# scard.net
KiCad netlist of a schematic drawn in EAGLE
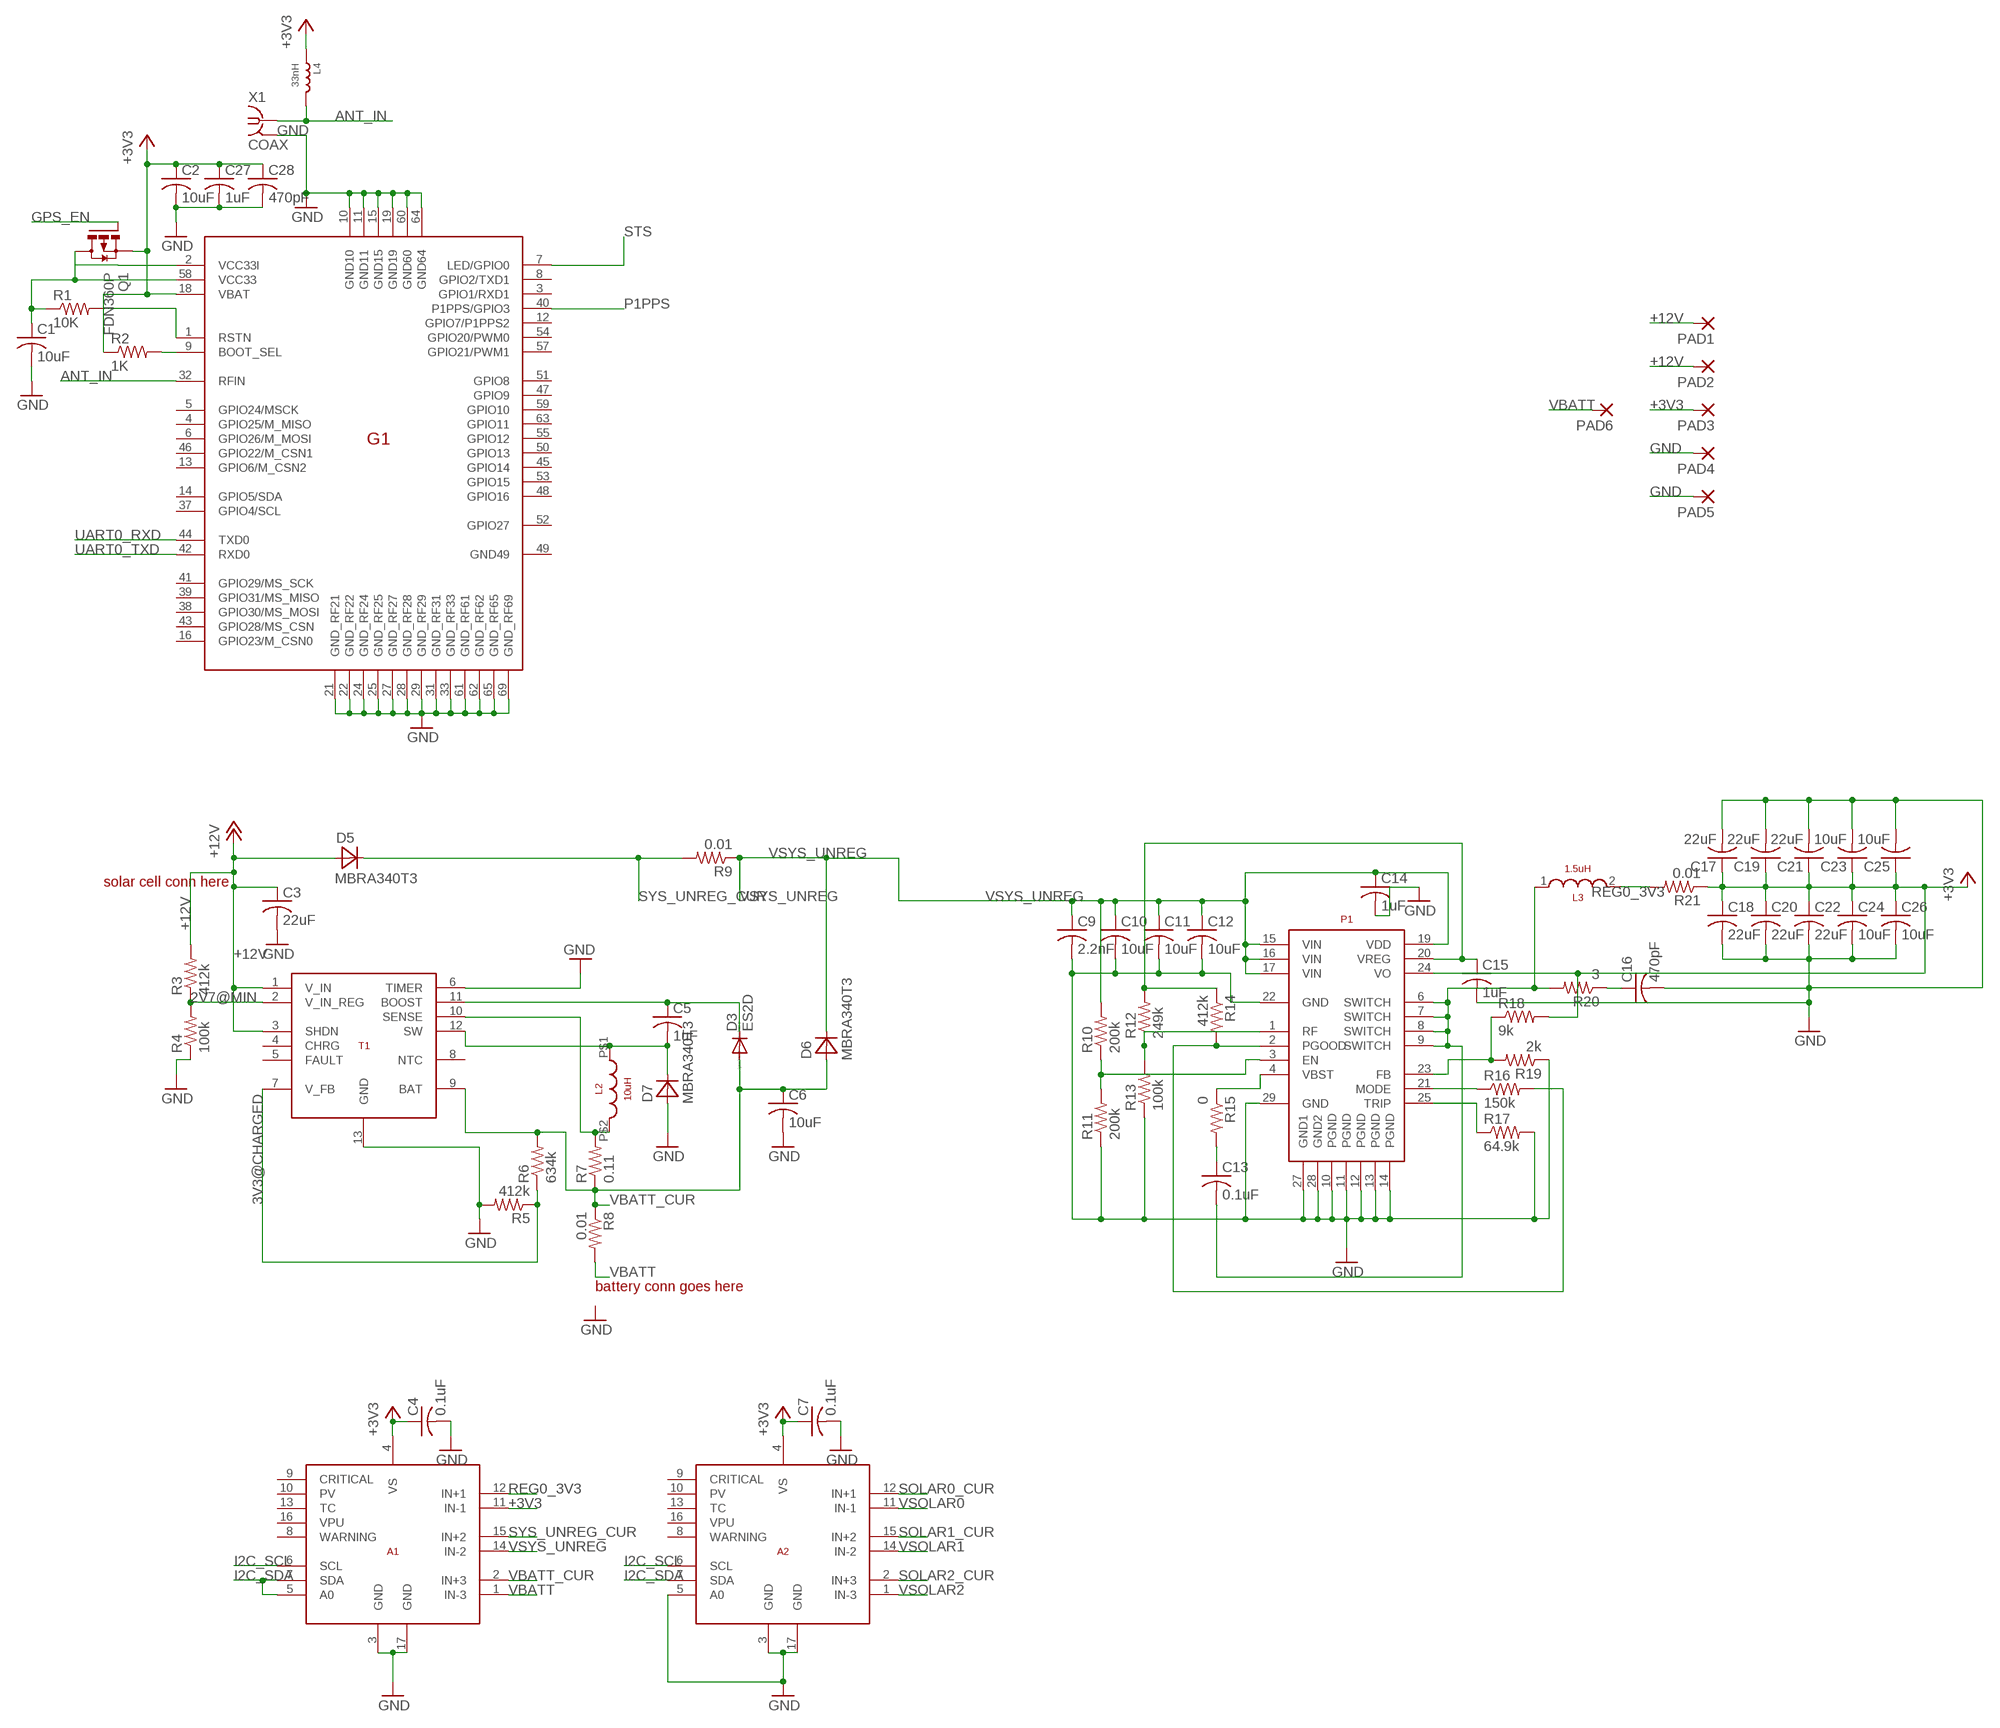
[diagram p0: schematic, sheet 1]

(export (version "E")
  (design (tool "Eeschema 10.0.6"))
  (components
    (comp (ref "A1")
      (value "INA3221-Q1")
      (footprint "eagle-import:VQFN16")
      (libsource (lib "eagle-import") (part "INA3221-Q1"))
    )
    (comp (ref "A2")
      (value "INA3221-Q1")
      (footprint "eagle-import:VQFN16")
      (libsource (lib "eagle-import") (part "INA3221-Q1"))
    )
    (comp (ref "C1")
      (value "10uF")
      (footprint "eagle-import:C0603")
      (libsource (lib "eagle-import") (part "C-USC0603"))
    )
    (comp (ref "C2")
      (value "10uF")
      (footprint "eagle-import:C0603")
      (libsource (lib "eagle-import") (part "resistor_348_C-USC0603"))
    )
    (comp (ref "C3")
      (value "22uF")
      (footprint "eagle-import:C0805")
      (libsource (lib "eagle-import") (part "resistor_348_C-USC0805"))
    )
    (comp (ref "C4")
      (value "0.1uF")
      (footprint "eagle-import:C0603")
      (libsource (lib "eagle-import") (part "resistor_348_C-USC0603"))
    )
    (comp (ref "C5")
      (value "1uF")
      (footprint "eagle-import:C0402")
      (libsource (lib "eagle-import") (part "C-USC0402"))
    )
    (comp (ref "C6")
      (value "10uF")
      (footprint "eagle-import:C0805")
      (libsource (lib "eagle-import") (part "resistor_348_C-USC0805"))
    )
    (comp (ref "C7")
      (value "0.1uF")
      (footprint "eagle-import:C0603")
      (libsource (lib "eagle-import") (part "resistor_348_C-USC0603"))
    )
    (comp (ref "C9")
      (value "2.2nF")
      (footprint "eagle-import:C0402")
      (libsource (lib "eagle-import") (part "resistor_348_C-USC0402"))
    )
    (comp (ref "C10")
      (value "10uF")
      (footprint "eagle-import:C0603")
      (libsource (lib "eagle-import") (part "resistor_348_C-USC0603"))
    )
    (comp (ref "C11")
      (value "10uF")
      (footprint "eagle-import:C0603")
      (libsource (lib "eagle-import") (part "resistor_348_C-USC0603"))
    )
    (comp (ref "C12")
      (value "10uF")
      (footprint "eagle-import:C0603")
      (libsource (lib "eagle-import") (part "resistor_348_C-USC0603"))
    )
    (comp (ref "C13")
      (value "0.1uF")
      (footprint "eagle-import:C0402")
      (libsource (lib "eagle-import") (part "resistor_348_C-USC0402"))
    )
    (comp (ref "C14")
      (value "1uF")
      (footprint "eagle-import:C0402")
      (libsource (lib "eagle-import") (part "resistor_348_C-USC0402"))
    )
    (comp (ref "C15")
      (value "1uF")
      (footprint "eagle-import:C0402")
      (libsource (lib "eagle-import") (part "resistor_348_C-USC0402"))
    )
    (comp (ref "C16")
      (value "470pF")
      (footprint "eagle-import:C0402")
      (libsource (lib "eagle-import") (part "resistor_348_C-USC0402"))
    )
    (comp (ref "C17")
      (value "22uF")
      (footprint "eagle-import:C0805")
      (libsource (lib "eagle-import") (part "C-USC0805"))
    )
    (comp (ref "C18")
      (value "22uF")
      (footprint "eagle-import:C0805")
      (libsource (lib "eagle-import") (part "C-USC0805"))
    )
    (comp (ref "C19")
      (value "22uF")
      (footprint "eagle-import:C0805")
      (libsource (lib "eagle-import") (part "C-USC0805"))
    )
    (comp (ref "C20")
      (value "22uF")
      (footprint "eagle-import:C0805")
      (libsource (lib "eagle-import") (part "C-USC0805"))
    )
    (comp (ref "C21")
      (value "22uF")
      (footprint "eagle-import:C0805")
      (libsource (lib "eagle-import") (part "C-USC0805"))
    )
    (comp (ref "C22")
      (value "22uF")
      (footprint "eagle-import:C0805")
      (libsource (lib "eagle-import") (part "C-USC0805"))
    )
    (comp (ref "C23")
      (value "10uF")
      (footprint "eagle-import:C0603")
      (libsource (lib "eagle-import") (part "resistor_348_C-USC0603"))
    )
    (comp (ref "C24")
      (value "10uF")
      (footprint "eagle-import:C0603")
      (libsource (lib "eagle-import") (part "resistor_348_C-USC0603"))
    )
    (comp (ref "C25")
      (value "10uF")
      (footprint "eagle-import:C0603")
      (libsource (lib "eagle-import") (part "resistor_348_C-USC0603"))
    )
    (comp (ref "C26")
      (value "10uF")
      (footprint "eagle-import:C0603")
      (libsource (lib "eagle-import") (part "resistor_348_C-USC0603"))
    )
    (comp (ref "C27")
      (value "1uF")
      (footprint "eagle-import:C0402")
      (libsource (lib "eagle-import") (part "resistor_348_C-USC0402"))
    )
    (comp (ref "C28")
      (value "470pF")
      (footprint "eagle-import:C0402")
      (libsource (lib "eagle-import") (part "resistor_348_C-USC0402"))
    )
    (comp (ref "D3")
      (value "ES2D")
      (footprint "eagle-import:SMB")
      (libsource (lib "eagle-import") (part "ES2D"))
    )
    (comp (ref "D5")
      (value "MBRA340T3")
      (footprint "eagle-import:SMA")
      (libsource (lib "eagle-import") (part "MBRA340T3"))
    )
    (comp (ref "D6")
      (value "MBRA340T3")
      (footprint "eagle-import:SMA")
      (libsource (lib "eagle-import") (part "MBRA340T3"))
    )
    (comp (ref "D7")
      (value "MBRA340T3")
      (footprint "eagle-import:SMA")
      (libsource (lib "eagle-import") (part "MBRA340T3"))
    )
    (comp (ref "G1")
      (value "VENUS838FLPX-L")
      (footprint "eagle-import:LGA69")
      (libsource (lib "eagle-import") (part "VENUS838FLPX-L"))
    )
    (comp (ref "L2")
      (value "10uH")
      (footprint "eagle-import:SRP7030")
      (libsource (lib "eagle-import") (part "SRP7030-100M"))
    )
    (comp (ref "L3")
      (value "1.5uH")
      (footprint "eagle-import:SRP7028A")
      (libsource (lib "eagle-import") (part "SRP7028A"))
    )
    (comp (ref "L4")
      (value "33nH")
      (footprint "eagle-import:L0805")
      (fields (field (name "MPN") "BLM21PG331SN1D"))
      (libsource (lib "eagle-import") (part "SMD-FERRITE-BEAD-330R-1500MA(0805)'0805'"))
    )
    (comp (ref "P1")
      (value "TPS548A20")
      (footprint "eagle-import:R-PWQFN-N28")
      (libsource (lib "eagle-import") (part "TPS548A20"))
    )
    (comp (ref "PAD1")
      (value "SMD5")
      (footprint "eagle-import:SMD2,54-5,08")
      (libsource (lib "eagle-import") (part "SMD5"))
    )
    (comp (ref "PAD2")
      (value "SMD5")
      (footprint "eagle-import:SMD2,54-5,08")
      (libsource (lib "eagle-import") (part "SMD5"))
    )
    (comp (ref "PAD3")
      (value "SMD5")
      (footprint "eagle-import:SMD2,54-5,08")
      (libsource (lib "eagle-import") (part "SMD5"))
    )
    (comp (ref "PAD4")
      (value "SMD5")
      (footprint "eagle-import:SMD2,54-5,08")
      (libsource (lib "eagle-import") (part "SMD5"))
    )
    (comp (ref "PAD5")
      (value "SMD5")
      (footprint "eagle-import:SMD2,54-5,08")
      (libsource (lib "eagle-import") (part "SMD5"))
    )
    (comp (ref "PAD6")
      (value "SMD5")
      (footprint "eagle-import:SMD2,54-5,08")
      (libsource (lib "eagle-import") (part "SMD5"))
    )
    (comp (ref "Q1")
      (value "FDN360P")
      (footprint "eagle-import:SUPER-SOT3")
      (libsource (lib "eagle-import") (part "FDN360P"))
    )
    (comp (ref "R1")
      (value "10K")
      (footprint "eagle-import:R0603")
      (libsource (lib "eagle-import") (part "R-US_R0603"))
    )
    (comp (ref "R2")
      (value "1K")
      (footprint "eagle-import:R0603")
      (libsource (lib "eagle-import") (part "resistor_348_R-US_R0603"))
    )
    (comp (ref "R3")
      (value "412k")
      (footprint "eagle-import:R0603")
      (libsource (lib "eagle-import") (part "R-US_R0603"))
    )
    (comp (ref "R4")
      (value "100k")
      (footprint "eagle-import:R0603")
      (libsource (lib "eagle-import") (part "R-US_R0603"))
    )
    (comp (ref "R5")
      (value "412k")
      (footprint "eagle-import:R0603")
      (libsource (lib "eagle-import") (part "R-US_R0603"))
    )
    (comp (ref "R6")
      (value "634k")
      (footprint "eagle-import:R0603")
      (libsource (lib "eagle-import") (part "R-US_R0603"))
    )
    (comp (ref "R7")
      (value "0.11")
      (footprint "eagle-import:R0603")
      (libsource (lib "eagle-import") (part "R-US_R0603"))
    )
    (comp (ref "R8")
      (value "0.01")
      (footprint "eagle-import:R0603")
      (libsource (lib "eagle-import") (part "R-US_R0603"))
    )
    (comp (ref "R9")
      (value "0.01")
      (footprint "eagle-import:R0603")
      (libsource (lib "eagle-import") (part "R-US_R0603"))
    )
    (comp (ref "R10")
      (value "200k")
      (footprint "eagle-import:R0603")
      (libsource (lib "eagle-import") (part "R-US_R0603"))
    )
    (comp (ref "R11")
      (value "200k")
      (footprint "eagle-import:R0603")
      (libsource (lib "eagle-import") (part "R-US_R0603"))
    )
    (comp (ref "R12")
      (value "249k")
      (footprint "eagle-import:R0603")
      (libsource (lib "eagle-import") (part "R-US_R0603"))
    )
    (comp (ref "R13")
      (value "100k")
      (footprint "eagle-import:R0603")
      (libsource (lib "eagle-import") (part "R-US_R0603"))
    )
    (comp (ref "R14")
      (value "412k")
      (footprint "eagle-import:R0603")
      (libsource (lib "eagle-import") (part "R-US_R0603"))
    )
    (comp (ref "R15")
      (value "0")
      (footprint "eagle-import:R0603")
      (libsource (lib "eagle-import") (part "R-US_R0603"))
    )
    (comp (ref "R16")
      (value "150k")
      (footprint "eagle-import:R0603")
      (libsource (lib "eagle-import") (part "R-US_R0603"))
    )
    (comp (ref "R17")
      (value "64.9k")
      (footprint "eagle-import:R0603")
      (libsource (lib "eagle-import") (part "R-US_R0603"))
    )
    (comp (ref "R18")
      (value "9k")
      (footprint "eagle-import:R0603")
      (libsource (lib "eagle-import") (part "R-US_R0603"))
    )
    (comp (ref "R19")
      (value "2k")
      (footprint "eagle-import:R0603")
      (libsource (lib "eagle-import") (part "R-US_R0603"))
    )
    (comp (ref "R20")
      (value "3")
      (footprint "eagle-import:R0603")
      (libsource (lib "eagle-import") (part "R-US_R0603"))
    )
    (comp (ref "R21")
      (value "0.01")
      (footprint "eagle-import:R0603")
      (libsource (lib "eagle-import") (part "R-US_R0603"))
    )
    (comp (ref "T1")
      (value "LT3652")
      (footprint "eagle-import:MSOP12")
      (libsource (lib "eagle-import") (part "LT3652"))
    )
    (comp (ref "X1")
      (value "COAX")
      (footprint "eagle-import:MMCX-J-P-X-ST-EM1-MKT")
      (libsource (lib "eagle-import") (part "COAX"))
    )
  )
  (nets
    (net (code "1") (name "+3V3") (class "Default")
      (node (ref "A1") (pin "11") (pinfunction "IN-1_11") (pintype "input"))
      (node (ref "A1") (pin "4") (pinfunction "VS_4") (pintype "power_in"))
      (node (ref "A2") (pin "4") (pinfunction "VS_4") (pintype "power_in"))
      (node (ref "C17") (pin "1") (pinfunction "1_1") (pintype "passive"))
      (node (ref "C18") (pin "1") (pinfunction "1_1") (pintype "passive"))
      (node (ref "C19") (pin "1") (pinfunction "1_1") (pintype "passive"))
      (node (ref "C2") (pin "1") (pinfunction "1_1") (pintype "passive"))
      (node (ref "C20") (pin "1") (pinfunction "1_1") (pintype "passive"))
      (node (ref "C21") (pin "1") (pinfunction "1_1") (pintype "passive"))
      (node (ref "C22") (pin "1") (pinfunction "1_1") (pintype "passive"))
      (node (ref "C23") (pin "1") (pinfunction "1_1") (pintype "passive"))
      (node (ref "C24") (pin "1") (pinfunction "1_1") (pintype "passive"))
      (node (ref "C25") (pin "1") (pinfunction "1_1") (pintype "passive"))
      (node (ref "C26") (pin "1") (pinfunction "1_1") (pintype "passive"))
      (node (ref "C27") (pin "1") (pinfunction "1_1") (pintype "passive"))
      (node (ref "C28") (pin "1") (pinfunction "1_1") (pintype "passive"))
      (node (ref "C4") (pin "1") (pinfunction "1_1") (pintype "passive"))
      (node (ref "C7") (pin "1") (pinfunction "1_1") (pintype "passive"))
      (node (ref "G1") (pin "18") (pinfunction "VBAT_18") (pintype "bidirectional"))
      (node (ref "L4") (pin "1") (pinfunction "1_1") (pintype "passive"))
      (node (ref "P1") (pin "24") (pinfunction "VO_24") (pintype "input"))
      (node (ref "PAD3") (pin "1") (pinfunction "P_1") (pintype "passive"))
      (node (ref "Q1") (pin "2") (pinfunction "S_2") (pintype "passive"))
      (node (ref "R18") (pin "2") (pinfunction "2_2") (pintype "passive"))
      (node (ref "R2") (pin "1") (pinfunction "1_1") (pintype "passive"))
      (node (ref "R21") (pin "1") (pinfunction "1_1") (pintype "passive"))
    )
    (net (code "2") (name "+12V") (class "Default")
      (node (ref "C3") (pin "1") (pinfunction "1_1") (pintype "passive"))
      (node (ref "D5") (pin "A") (pinfunction "A_A") (pintype "passive"))
      (node (ref "PAD1") (pin "1") (pinfunction "P_1") (pintype "passive"))
      (node (ref "PAD2") (pin "1") (pinfunction "P_1") (pintype "passive"))
      (node (ref "R3") (pin "2") (pinfunction "2_2") (pintype "passive"))
      (node (ref "T1") (pin "1") (pinfunction "V_IN_1") (pintype "bidirectional"))
      (node (ref "T1") (pin "3") (pinfunction "SHDN_3") (pintype "bidirectional"))
    )
    (net (code "3") (name "/2V7@MIN") (class "Default")
      (node (ref "R3") (pin "1") (pinfunction "1_1") (pintype "passive"))
      (node (ref "R4") (pin "2") (pinfunction "2_2") (pintype "passive"))
      (node (ref "T1") (pin "2") (pinfunction "V_IN_REG_2") (pintype "bidirectional"))
    )
    (net (code "4") (name "/3V3@CHARGED") (class "Default")
      (node (ref "R5") (pin "1") (pinfunction "1_1") (pintype "passive"))
      (node (ref "R6") (pin "1") (pinfunction "1_1") (pintype "passive"))
      (node (ref "T1") (pin "7") (pinfunction "V_FB_7") (pintype "bidirectional"))
    )
    (net (code "5") (name "/ANT_IN") (class "Default")
      (node (ref "G1") (pin "32") (pinfunction "RFIN_32") (pintype "bidirectional"))
      (node (ref "L4") (pin "2") (pinfunction "2_2") (pintype "passive"))
      (node (ref "X1") (pin "1") (pinfunction "1_1") (pintype "passive"))
    )
    (net (code "6") (name "/GPS_EN") (class "Default")
      (node (ref "Q1") (pin "1") (pinfunction "G_1") (pintype "passive"))
    )
    (net (code "7") (name "/I2C_SCL") (class "Default")
      (node (ref "A1") (pin "6") (pinfunction "SCL_6") (pintype "bidirectional"))
      (node (ref "A2") (pin "6") (pinfunction "SCL_6") (pintype "bidirectional"))
    )
    (net (code "8") (name "/I2C_SDA") (class "Default")
      (node (ref "A1") (pin "5") (pinfunction "A0_5") (pintype "bidirectional"))
      (node (ref "A1") (pin "7") (pinfunction "SDA_7") (pintype "bidirectional"))
      (node (ref "A2") (pin "7") (pinfunction "SDA_7") (pintype "bidirectional"))
    )
    (net (code "9") (name "/P1PPS") (class "Default")
      (node (ref "G1") (pin "40") (pinfunction "P1PPS/GPIO3_40") (pintype "bidirectional"))
    )
    (net (code "10") (name "/REG0_3V3") (class "Default")
      (node (ref "A1") (pin "12") (pinfunction "IN+1_12") (pintype "input"))
      (node (ref "L3") (pin "2") (pintype "passive"))
      (node (ref "R21") (pin "2") (pinfunction "2_2") (pintype "passive"))
    )
    (net (code "11") (name "/SOLAR0_CUR") (class "Default")
      (node (ref "A2") (pin "12") (pinfunction "IN+1_12") (pintype "input"))
    )
    (net (code "12") (name "/SOLAR1_CUR") (class "Default")
      (node (ref "A2") (pin "15") (pinfunction "IN+2_15") (pintype "input"))
    )
    (net (code "13") (name "/SOLAR2_CUR") (class "Default")
      (node (ref "A2") (pin "2") (pinfunction "IN+3_2") (pintype "input"))
    )
    (net (code "14") (name "/STS") (class "Default")
      (node (ref "G1") (pin "7") (pinfunction "LED/GPIO0_7") (pintype "bidirectional"))
    )
    (net (code "15") (name "/SYS_UNREG_CUR") (class "Default")
      (node (ref "A1") (pin "15") (pinfunction "IN+2_15") (pintype "input"))
      (node (ref "D5") (pin "C") (pinfunction "C_C") (pintype "passive"))
      (node (ref "R9") (pin "2") (pinfunction "2_2") (pintype "passive"))
    )
    (net (code "16") (name "/UART0_RXD") (class "Default")
      (node (ref "G1") (pin "44") (pinfunction "TXD0_44") (pintype "bidirectional"))
    )
    (net (code "17") (name "/UART0_TXD") (class "Default")
      (node (ref "G1") (pin "42") (pinfunction "RXD0_42") (pintype "bidirectional"))
    )
    (net (code "18") (name "/VBATT") (class "Default")
      (node (ref "A1") (pin "1") (pinfunction "IN-3_1") (pintype "input"))
      (node (ref "PAD6") (pin "1") (pinfunction "P_1") (pintype "passive"))
      (node (ref "R8") (pin "2") (pinfunction "2_2") (pintype "passive"))
    )
    (net (code "19") (name "/VBATT_CUR") (class "Default")
      (node (ref "A1") (pin "2") (pinfunction "IN+3_2") (pintype "input"))
      (node (ref "C6") (pin "1") (pinfunction "1_1") (pintype "passive"))
      (node (ref "D3") (pin "A") (pinfunction "A_A") (pintype "passive"))
      (node (ref "D6") (pin "A") (pinfunction "A_A") (pintype "passive"))
      (node (ref "R6") (pin "2") (pinfunction "2_2") (pintype "passive"))
      (node (ref "R7") (pin "1") (pinfunction "1_1") (pintype "passive"))
      (node (ref "R8") (pin "1") (pinfunction "1_1") (pintype "passive"))
      (node (ref "T1") (pin "9") (pinfunction "BAT_9") (pintype "bidirectional"))
    )
    (net (code "20") (name "/VSOLAR0") (class "Default")
      (node (ref "A2") (pin "11") (pinfunction "IN-1_11") (pintype "input"))
    )
    (net (code "21") (name "/VSOLAR1") (class "Default")
      (node (ref "A2") (pin "14") (pinfunction "IN-2_14") (pintype "input"))
    )
    (net (code "22") (name "/VSOLAR2") (class "Default")
      (node (ref "A2") (pin "1") (pinfunction "IN-3_1") (pintype "input"))
    )
    (net (code "23") (name "/VSYS_UNREG") (class "Default")
      (node (ref "A1") (pin "14") (pinfunction "IN-2_14") (pintype "input"))
      (node (ref "C10") (pin "1") (pinfunction "1_1") (pintype "passive"))
      (node (ref "C11") (pin "1") (pinfunction "1_1") (pintype "passive"))
      (node (ref "C12") (pin "1") (pinfunction "1_1") (pintype "passive"))
      (node (ref "C14") (pin "1") (pinfunction "1_1") (pintype "passive"))
      (node (ref "C9") (pin "1") (pinfunction "1_1") (pintype "passive"))
      (node (ref "D6") (pin "C") (pinfunction "C_C") (pintype "passive"))
      (node (ref "P1") (pin "15") (pinfunction "VIN_15") (pintype "power_in"))
      (node (ref "P1") (pin "16") (pinfunction "VIN_16") (pintype "power_in"))
      (node (ref "P1") (pin "17") (pinfunction "VIN_17") (pintype "power_in"))
      (node (ref "P1") (pin "19") (pinfunction "VDD_19") (pintype "power_in"))
      (node (ref "R10") (pin "2") (pinfunction "2_2") (pintype "passive"))
      (node (ref "R9") (pin "1") (pinfunction "1_1") (pintype "passive"))
    )
    (net (code "24") (name "GND") (class "Default")
      (node (ref "A1") (pin "17") (pinfunction "GND_17") (pintype "power_in"))
      (node (ref "A1") (pin "3") (pinfunction "GND_3") (pintype "power_in"))
      (node (ref "A2") (pin "17") (pinfunction "GND_17") (pintype "power_in"))
      (node (ref "A2") (pin "3") (pinfunction "GND_3") (pintype "power_in"))
      (node (ref "A2") (pin "5") (pinfunction "A0_5") (pintype "bidirectional"))
      (node (ref "C1") (pin "2") (pinfunction "2_2") (pintype "passive"))
      (node (ref "C10") (pin "2") (pinfunction "2_2") (pintype "passive"))
      (node (ref "C11") (pin "2") (pinfunction "2_2") (pintype "passive"))
      (node (ref "C12") (pin "2") (pinfunction "2_2") (pintype "passive"))
      (node (ref "C14") (pin "2") (pinfunction "2_2") (pintype "passive"))
      (node (ref "C15") (pin "2") (pinfunction "2_2") (pintype "passive"))
      (node (ref "C16") (pin "2") (pinfunction "2_2") (pintype "passive"))
      (node (ref "C17") (pin "2") (pinfunction "2_2") (pintype "passive"))
      (node (ref "C18") (pin "2") (pinfunction "2_2") (pintype "passive"))
      (node (ref "C19") (pin "2") (pinfunction "2_2") (pintype "passive"))
      (node (ref "C2") (pin "2") (pinfunction "2_2") (pintype "passive"))
      (node (ref "C20") (pin "2") (pinfunction "2_2") (pintype "passive"))
      (node (ref "C21") (pin "2") (pinfunction "2_2") (pintype "passive"))
      (node (ref "C22") (pin "2") (pinfunction "2_2") (pintype "passive"))
      (node (ref "C23") (pin "2") (pinfunction "2_2") (pintype "passive"))
      (node (ref "C24") (pin "2") (pinfunction "2_2") (pintype "passive"))
      (node (ref "C25") (pin "2") (pinfunction "2_2") (pintype "passive"))
      (node (ref "C26") (pin "2") (pinfunction "2_2") (pintype "passive"))
      (node (ref "C27") (pin "2") (pinfunction "2_2") (pintype "passive"))
      (node (ref "C28") (pin "2") (pinfunction "2_2") (pintype "passive"))
      (node (ref "C3") (pin "2") (pinfunction "2_2") (pintype "passive"))
      (node (ref "C4") (pin "2") (pinfunction "2_2") (pintype "passive"))
      (node (ref "C6") (pin "2") (pinfunction "2_2") (pintype "passive"))
      (node (ref "C7") (pin "2") (pinfunction "2_2") (pintype "passive"))
      (node (ref "C9") (pin "2") (pinfunction "2_2") (pintype "passive"))
      (node (ref "D7") (pin "A") (pinfunction "A_A") (pintype "passive"))
      (node (ref "G1") (pin "10") (pinfunction "GND10_10") (pintype "bidirectional"))
      (node (ref "G1") (pin "11") (pinfunction "GND11_11") (pintype "bidirectional"))
      (node (ref "G1") (pin "15") (pinfunction "GND15_15") (pintype "bidirectional"))
      (node (ref "G1") (pin "19") (pinfunction "GND19_19") (pintype "bidirectional"))
      (node (ref "G1") (pin "21") (pinfunction "GND_RF21_21") (pintype "bidirectional"))
      (node (ref "G1") (pin "22") (pinfunction "GND_RF22_22") (pintype "bidirectional"))
      (node (ref "G1") (pin "24") (pinfunction "GND_RF24_24") (pintype "bidirectional"))
      (node (ref "G1") (pin "25") (pinfunction "GND_RF25_25") (pintype "bidirectional"))
      (node (ref "G1") (pin "27") (pinfunction "GND_RF27_27") (pintype "bidirectional"))
      (node (ref "G1") (pin "28") (pinfunction "GND_RF28_28") (pintype "bidirectional"))
      (node (ref "G1") (pin "29") (pinfunction "GND_RF29_29") (pintype "bidirectional"))
      (node (ref "G1") (pin "31") (pinfunction "GND_RF31_31") (pintype "bidirectional"))
      (node (ref "G1") (pin "33") (pinfunction "GND_RF33_33") (pintype "bidirectional"))
      (node (ref "G1") (pin "60") (pinfunction "GND60_60") (pintype "bidirectional"))
      (node (ref "G1") (pin "61") (pinfunction "GND_RF61_61") (pintype "bidirectional"))
      (node (ref "G1") (pin "62") (pinfunction "GND_RF62_62") (pintype "bidirectional"))
      (node (ref "G1") (pin "64") (pinfunction "GND64_64") (pintype "bidirectional"))
      (node (ref "G1") (pin "65") (pinfunction "GND_RF65_65") (pintype "bidirectional"))
      (node (ref "G1") (pin "69") (pinfunction "GND_RF69_69") (pintype "bidirectional"))
      (node (ref "P1") (pin "10") (pinfunction "PGND_10") (pintype "power_in"))
      (node (ref "P1") (pin "11") (pinfunction "PGND_11") (pintype "power_in"))
      (node (ref "P1") (pin "12") (pinfunction "PGND_12") (pintype "power_in"))
      (node (ref "P1") (pin "13") (pinfunction "PGND_13") (pintype "power_in"))
      (node (ref "P1") (pin "14") (pinfunction "PGND_14") (pintype "power_in"))
      (node (ref "P1") (pin "22") (pinfunction "GND_22") (pintype "power_in"))
      (node (ref "P1") (pin "27") (pinfunction "GND1_27") (pintype "power_in"))
      (node (ref "P1") (pin "28") (pinfunction "GND2_28") (pintype "power_in"))
      (node (ref "P1") (pin "29") (pinfunction "GND_29") (pintype "power_in"))
      (node (ref "PAD4") (pin "1") (pinfunction "P_1") (pintype "passive"))
      (node (ref "PAD5") (pin "1") (pinfunction "P_1") (pintype "passive"))
      (node (ref "R11") (pin "1") (pinfunction "1_1") (pintype "passive"))
      (node (ref "R13") (pin "1") (pinfunction "1_1") (pintype "passive"))
      (node (ref "R17") (pin "2") (pinfunction "2_2") (pintype "passive"))
      (node (ref "R19") (pin "1") (pinfunction "1_1") (pintype "passive"))
      (node (ref "R4") (pin "1") (pinfunction "1_1") (pintype "passive"))
      (node (ref "R5") (pin "2") (pinfunction "2_2") (pintype "passive"))
      (node (ref "T1") (pin "13") (pinfunction "GND_13") (pintype "bidirectional"))
      (node (ref "T1") (pin "6") (pinfunction "TIMER_6") (pintype "bidirectional"))
      (node (ref "X1") (pin "2@1") (pinfunction "GND_2@1") (pintype "power_in"))
    )
    (net (code "25") (name "Net-(C13-Pad1)") (class "Default")
      (node (ref "C13") (pin "1") (pinfunction "1_1") (pintype "passive"))
      (node (ref "R15") (pin "2") (pinfunction "2_2") (pintype "passive"))
    )
    (net (code "26") (name "Net-(C13-Pad2)") (class "Default")
      (node (ref "C13") (pin "2") (pinfunction "2_2") (pintype "passive"))
      (node (ref "L3") (pin "1") (pintype "passive"))
      (node (ref "P1") (pin "6") (pinfunction "SWITCH_6") (pintype "bidirectional"))
      (node (ref "P1") (pin "7") (pinfunction "SWITCH_7") (pintype "bidirectional"))
      (node (ref "P1") (pin "8") (pinfunction "SWITCH_8") (pintype "bidirectional"))
      (node (ref "P1") (pin "9") (pinfunction "SWITCH_9") (pintype "bidirectional"))
      (node (ref "R20") (pin "2") (pinfunction "2_2") (pintype "passive"))
    )
    (net (code "27") (name "Net-(C16-Pad1)") (class "Default")
      (node (ref "C16") (pin "1") (pinfunction "1_1") (pintype "passive"))
      (node (ref "R20") (pin "1") (pinfunction "1_1") (pintype "passive"))
    )
    (net (code "28") (name "Net-(G1-BOOT_SEL)") (class "Default")
      (node (ref "G1") (pin "9") (pinfunction "BOOT_SEL_9") (pintype "bidirectional"))
      (node (ref "R2") (pin "2") (pinfunction "2_2") (pintype "passive"))
    )
    (net (code "29") (name "Net-(G1-RSTN)") (class "Default")
      (node (ref "G1") (pin "1") (pinfunction "RSTN_1") (pintype "bidirectional"))
      (node (ref "R1") (pin "2") (pinfunction "2_2") (pintype "passive"))
    )
    (net (code "30") (name "Net-(G1-VCC33)") (class "Default")
      (node (ref "C1") (pin "1") (pinfunction "1_1") (pintype "passive"))
      (node (ref "G1") (pin "2") (pinfunction "VCC33I_2") (pintype "bidirectional"))
      (node (ref "G1") (pin "58") (pinfunction "VCC33_58") (pintype "bidirectional"))
      (node (ref "Q1") (pin "3") (pinfunction "D_3") (pintype "passive"))
      (node (ref "R1") (pin "1") (pinfunction "1_1") (pintype "passive"))
    )
    (net (code "31") (name "Net-(P1-EN)") (class "Default")
      (node (ref "P1") (pin "3") (pinfunction "EN_3") (pintype "input"))
      (node (ref "R10") (pin "1") (pinfunction "1_1") (pintype "passive"))
      (node (ref "R11") (pin "2") (pinfunction "2_2") (pintype "passive"))
    )
    (net (code "32") (name "Net-(P1-FB)") (class "Default")
      (node (ref "P1") (pin "23") (pinfunction "FB_23") (pintype "input"))
      (node (ref "R18") (pin "1") (pinfunction "1_1") (pintype "passive"))
      (node (ref "R19") (pin "2") (pinfunction "2_2") (pintype "passive"))
    )
    (net (code "33") (name "Net-(P1-MODE)") (class "Default")
      (node (ref "P1") (pin "21") (pinfunction "MODE_21") (pintype "input"))
      (node (ref "R16") (pin "1") (pinfunction "1_1") (pintype "passive"))
    )
    (net (code "34") (name "Net-(P1-PGOOD)") (class "Default")
      (node (ref "P1") (pin "2") (pinfunction "PGOOD_2") (pintype "output"))
      (node (ref "R14") (pin "2") (pinfunction "2_2") (pintype "passive"))
      (node (ref "R16") (pin "2") (pinfunction "2_2") (pintype "passive"))
    )
    (net (code "35") (name "Net-(P1-RF)") (class "Default")
      (node (ref "P1") (pin "1") (pinfunction "RF_1") (pintype "input"))
      (node (ref "R12") (pin "1") (pinfunction "1_1") (pintype "passive"))
      (node (ref "R13") (pin "2") (pinfunction "2_2") (pintype "passive"))
    )
    (net (code "36") (name "Net-(P1-TRIP)") (class "Default")
      (node (ref "P1") (pin "25") (pinfunction "TRIP_25") (pintype "bidirectional"))
      (node (ref "R17") (pin "1") (pinfunction "1_1") (pintype "passive"))
    )
    (net (code "37") (name "Net-(P1-VBST)") (class "Default")
      (node (ref "P1") (pin "4") (pinfunction "VBST_4") (pintype "power_in"))
      (node (ref "R15") (pin "1") (pinfunction "1_1") (pintype "passive"))
    )
    (net (code "38") (name "Net-(P1-VREG)") (class "Default")
      (node (ref "C15") (pin "1") (pinfunction "1_1") (pintype "passive"))
      (node (ref "P1") (pin "20") (pinfunction "VREG_20") (pintype "output"))
      (node (ref "R12") (pin "2") (pinfunction "2_2") (pintype "passive"))
      (node (ref "R14") (pin "1") (pinfunction "1_1") (pintype "passive"))
    )
    (net (code "39") (name "Net-(T1-BOOST)") (class "Default")
      (node (ref "C5") (pin "1") (pinfunction "1_1") (pintype "passive"))
      (node (ref "D3") (pin "C") (pinfunction "C_C") (pintype "passive"))
      (node (ref "T1") (pin "11") (pinfunction "BOOST_11") (pintype "bidirectional"))
    )
    (net (code "40") (name "Net-(T1-SENSE)") (class "Default")
      (node (ref "L2") (pin "P$2") (pintype "passive"))
      (node (ref "R7") (pin "2") (pinfunction "2_2") (pintype "passive"))
      (node (ref "T1") (pin "10") (pinfunction "SENSE_10") (pintype "bidirectional"))
    )
    (net (code "41") (name "Net-(T1-SW)") (class "Default")
      (node (ref "C5") (pin "2") (pinfunction "2_2") (pintype "passive"))
      (node (ref "D7") (pin "C") (pinfunction "C_C") (pintype "passive"))
      (node (ref "L2") (pin "P$1") (pintype "passive"))
      (node (ref "T1") (pin "12") (pinfunction "SW_12") (pintype "bidirectional"))
    )
    (net (code "42") (name "unconnected-(A1-CRITICAL-Pad9)") (class "Default")
      (node (ref "A1") (pin "9") (pinfunction "CRITICAL_9") (pintype "bidirectional"))
    )
    (net (code "43") (name "unconnected-(A1-PV-Pad10)") (class "Default")
      (node (ref "A1") (pin "10") (pinfunction "PV_10") (pintype "bidirectional"))
    )
    (net (code "44") (name "unconnected-(A1-TC-Pad13)") (class "Default")
      (node (ref "A1") (pin "13") (pinfunction "TC_13") (pintype "bidirectional"))
    )
    (net (code "45") (name "unconnected-(A1-VPU-Pad16)") (class "Default")
      (node (ref "A1") (pin "16") (pinfunction "VPU_16") (pintype "bidirectional"))
    )
    (net (code "46") (name "unconnected-(A1-WARNING-Pad8)") (class "Default")
      (node (ref "A1") (pin "8") (pinfunction "WARNING_8") (pintype "bidirectional"))
    )
    (net (code "47") (name "unconnected-(A2-CRITICAL-Pad9)") (class "Default")
      (node (ref "A2") (pin "9") (pinfunction "CRITICAL_9") (pintype "bidirectional"))
    )
    (net (code "48") (name "unconnected-(A2-PV-Pad10)") (class "Default")
      (node (ref "A2") (pin "10") (pinfunction "PV_10") (pintype "bidirectional"))
    )
    (net (code "49") (name "unconnected-(A2-TC-Pad13)") (class "Default")
      (node (ref "A2") (pin "13") (pinfunction "TC_13") (pintype "bidirectional"))
    )
    (net (code "50") (name "unconnected-(A2-VPU-Pad16)") (class "Default")
      (node (ref "A2") (pin "16") (pinfunction "VPU_16") (pintype "bidirectional"))
    )
    (net (code "51") (name "unconnected-(A2-WARNING-Pad8)") (class "Default")
      (node (ref "A2") (pin "8") (pinfunction "WARNING_8") (pintype "bidirectional"))
    )
    (net (code "52") (name "unconnected-(G1-GND49-Pad49)") (class "Default")
      (node (ref "G1") (pin "49") (pinfunction "GND49_49") (pintype "bidirectional"))
    )
    (net (code "53") (name "unconnected-(G1-GPIO1{slash}RXD1-Pad3)") (class "Default")
      (node (ref "G1") (pin "3") (pinfunction "GPIO1/RXD1_3") (pintype "bidirectional"))
    )
    (net (code "54") (name "unconnected-(G1-GPIO2{slash}TXD1-Pad8)") (class "Default")
      (node (ref "G1") (pin "8") (pinfunction "GPIO2/TXD1_8") (pintype "bidirectional"))
    )
    (net (code "55") (name "unconnected-(G1-GPIO4{slash}SCL-Pad37)") (class "Default")
      (node (ref "G1") (pin "37") (pinfunction "GPIO4/SCL_37") (pintype "bidirectional"))
    )
    (net (code "56") (name "unconnected-(G1-GPIO5{slash}SDA-Pad14)") (class "Default")
      (node (ref "G1") (pin "14") (pinfunction "GPIO5/SDA_14") (pintype "bidirectional"))
    )
    (net (code "57") (name "unconnected-(G1-GPIO6{slash}M_CSN2-Pad13)") (class "Default")
      (node (ref "G1") (pin "13") (pinfunction "GPIO6/M_CSN2_13") (pintype "bidirectional"))
    )
    (net (code "58") (name "unconnected-(G1-GPIO7{slash}P1PPS2-Pad12)") (class "Default")
      (node (ref "G1") (pin "12") (pinfunction "GPIO7/P1PPS2_12") (pintype "bidirectional"))
    )
    (net (code "59") (name "unconnected-(G1-GPIO8-Pad51)") (class "Default")
      (node (ref "G1") (pin "51") (pinfunction "GPIO8_51") (pintype "bidirectional"))
    )
    (net (code "60") (name "unconnected-(G1-GPIO9-Pad47)") (class "Default")
      (node (ref "G1") (pin "47") (pinfunction "GPIO9_47") (pintype "bidirectional"))
    )
    (net (code "61") (name "unconnected-(G1-GPIO10-Pad59)") (class "Default")
      (node (ref "G1") (pin "59") (pinfunction "GPIO10_59") (pintype "bidirectional"))
    )
    (net (code "62") (name "unconnected-(G1-GPIO11-Pad63)") (class "Default")
      (node (ref "G1") (pin "63") (pinfunction "GPIO11_63") (pintype "bidirectional"))
    )
    (net (code "63") (name "unconnected-(G1-GPIO12-Pad55)") (class "Default")
      (node (ref "G1") (pin "55") (pinfunction "GPIO12_55") (pintype "bidirectional"))
    )
    (net (code "64") (name "unconnected-(G1-GPIO13-Pad50)") (class "Default")
      (node (ref "G1") (pin "50") (pinfunction "GPIO13_50") (pintype "bidirectional"))
    )
    (net (code "65") (name "unconnected-(G1-GPIO14-Pad45)") (class "Default")
      (node (ref "G1") (pin "45") (pinfunction "GPIO14_45") (pintype "bidirectional"))
    )
    (net (code "66") (name "unconnected-(G1-GPIO15-Pad53)") (class "Default")
      (node (ref "G1") (pin "53") (pinfunction "GPIO15_53") (pintype "bidirectional"))
    )
    (net (code "67") (name "unconnected-(G1-GPIO16-Pad48)") (class "Default")
      (node (ref "G1") (pin "48") (pinfunction "GPIO16_48") (pintype "bidirectional"))
    )
    (net (code "68") (name "unconnected-(G1-GPIO20{slash}PWM0-Pad54)") (class "Default")
      (node (ref "G1") (pin "54") (pinfunction "GPIO20/PWM0_54") (pintype "bidirectional"))
    )
    (net (code "69") (name "unconnected-(G1-GPIO21{slash}PWM1-Pad57)") (class "Default")
      (node (ref "G1") (pin "57") (pinfunction "GPIO21/PWM1_57") (pintype "bidirectional"))
    )
    (net (code "70") (name "unconnected-(G1-GPIO22{slash}M_CSN1-Pad46)") (class "Default")
      (node (ref "G1") (pin "46") (pinfunction "GPIO22/M_CSN1_46") (pintype "bidirectional"))
    )
    (net (code "71") (name "unconnected-(G1-GPIO23{slash}M_CSN0-Pad16)") (class "Default")
      (node (ref "G1") (pin "16") (pinfunction "GPIO23/M_CSN0_16") (pintype "bidirectional"))
    )
    (net (code "72") (name "unconnected-(G1-GPIO24{slash}MSCK-Pad5)") (class "Default")
      (node (ref "G1") (pin "5") (pinfunction "GPIO24/MSCK_5") (pintype "bidirectional"))
    )
    (net (code "73") (name "unconnected-(G1-GPIO25{slash}M_MISO-Pad4)") (class "Default")
      (node (ref "G1") (pin "4") (pinfunction "GPIO25/M_MISO_4") (pintype "bidirectional"))
    )
    (net (code "74") (name "unconnected-(G1-GPIO26{slash}M_MOSI-Pad6)") (class "Default")
      (node (ref "G1") (pin "6") (pinfunction "GPIO26/M_MOSI_6") (pintype "bidirectional"))
    )
    (net (code "75") (name "unconnected-(G1-GPIO27-Pad52)") (class "Default")
      (node (ref "G1") (pin "52") (pinfunction "GPIO27_52") (pintype "bidirectional"))
    )
    (net (code "76") (name "unconnected-(G1-GPIO28{slash}MS_CSN-Pad43)") (class "Default")
      (node (ref "G1") (pin "43") (pinfunction "GPIO28/MS_CSN_43") (pintype "bidirectional"))
    )
    (net (code "77") (name "unconnected-(G1-GPIO29{slash}MS_SCK-Pad41)") (class "Default")
      (node (ref "G1") (pin "41") (pinfunction "GPIO29/MS_SCK_41") (pintype "bidirectional"))
    )
    (net (code "78") (name "unconnected-(G1-GPIO30{slash}MS_MOSI-Pad38)") (class "Default")
      (node (ref "G1") (pin "38") (pinfunction "GPIO30/MS_MOSI_38") (pintype "bidirectional"))
    )
    (net (code "79") (name "unconnected-(G1-GPIO31{slash}MS_MISO-Pad39)") (class "Default")
      (node (ref "G1") (pin "39") (pinfunction "GPIO31/MS_MISO_39") (pintype "bidirectional"))
    )
    (net (code "80") (name "unconnected-(T1-CHRG-Pad4)") (class "Default")
      (node (ref "T1") (pin "4") (pinfunction "CHRG_4") (pintype "bidirectional"))
    )
    (net (code "81") (name "unconnected-(T1-FAULT-Pad5)") (class "Default")
      (node (ref "T1") (pin "5") (pinfunction "FAULT_5") (pintype "bidirectional"))
    )
    (net (code "82") (name "unconnected-(T1-NTC-Pad8)") (class "Default")
      (node (ref "T1") (pin "8") (pinfunction "NTC_8") (pintype "bidirectional"))
    )
  )
)
